# 02_-_IntelliModule_Connector.net
KiCad netlist of a schematic drawn in Altium Designer
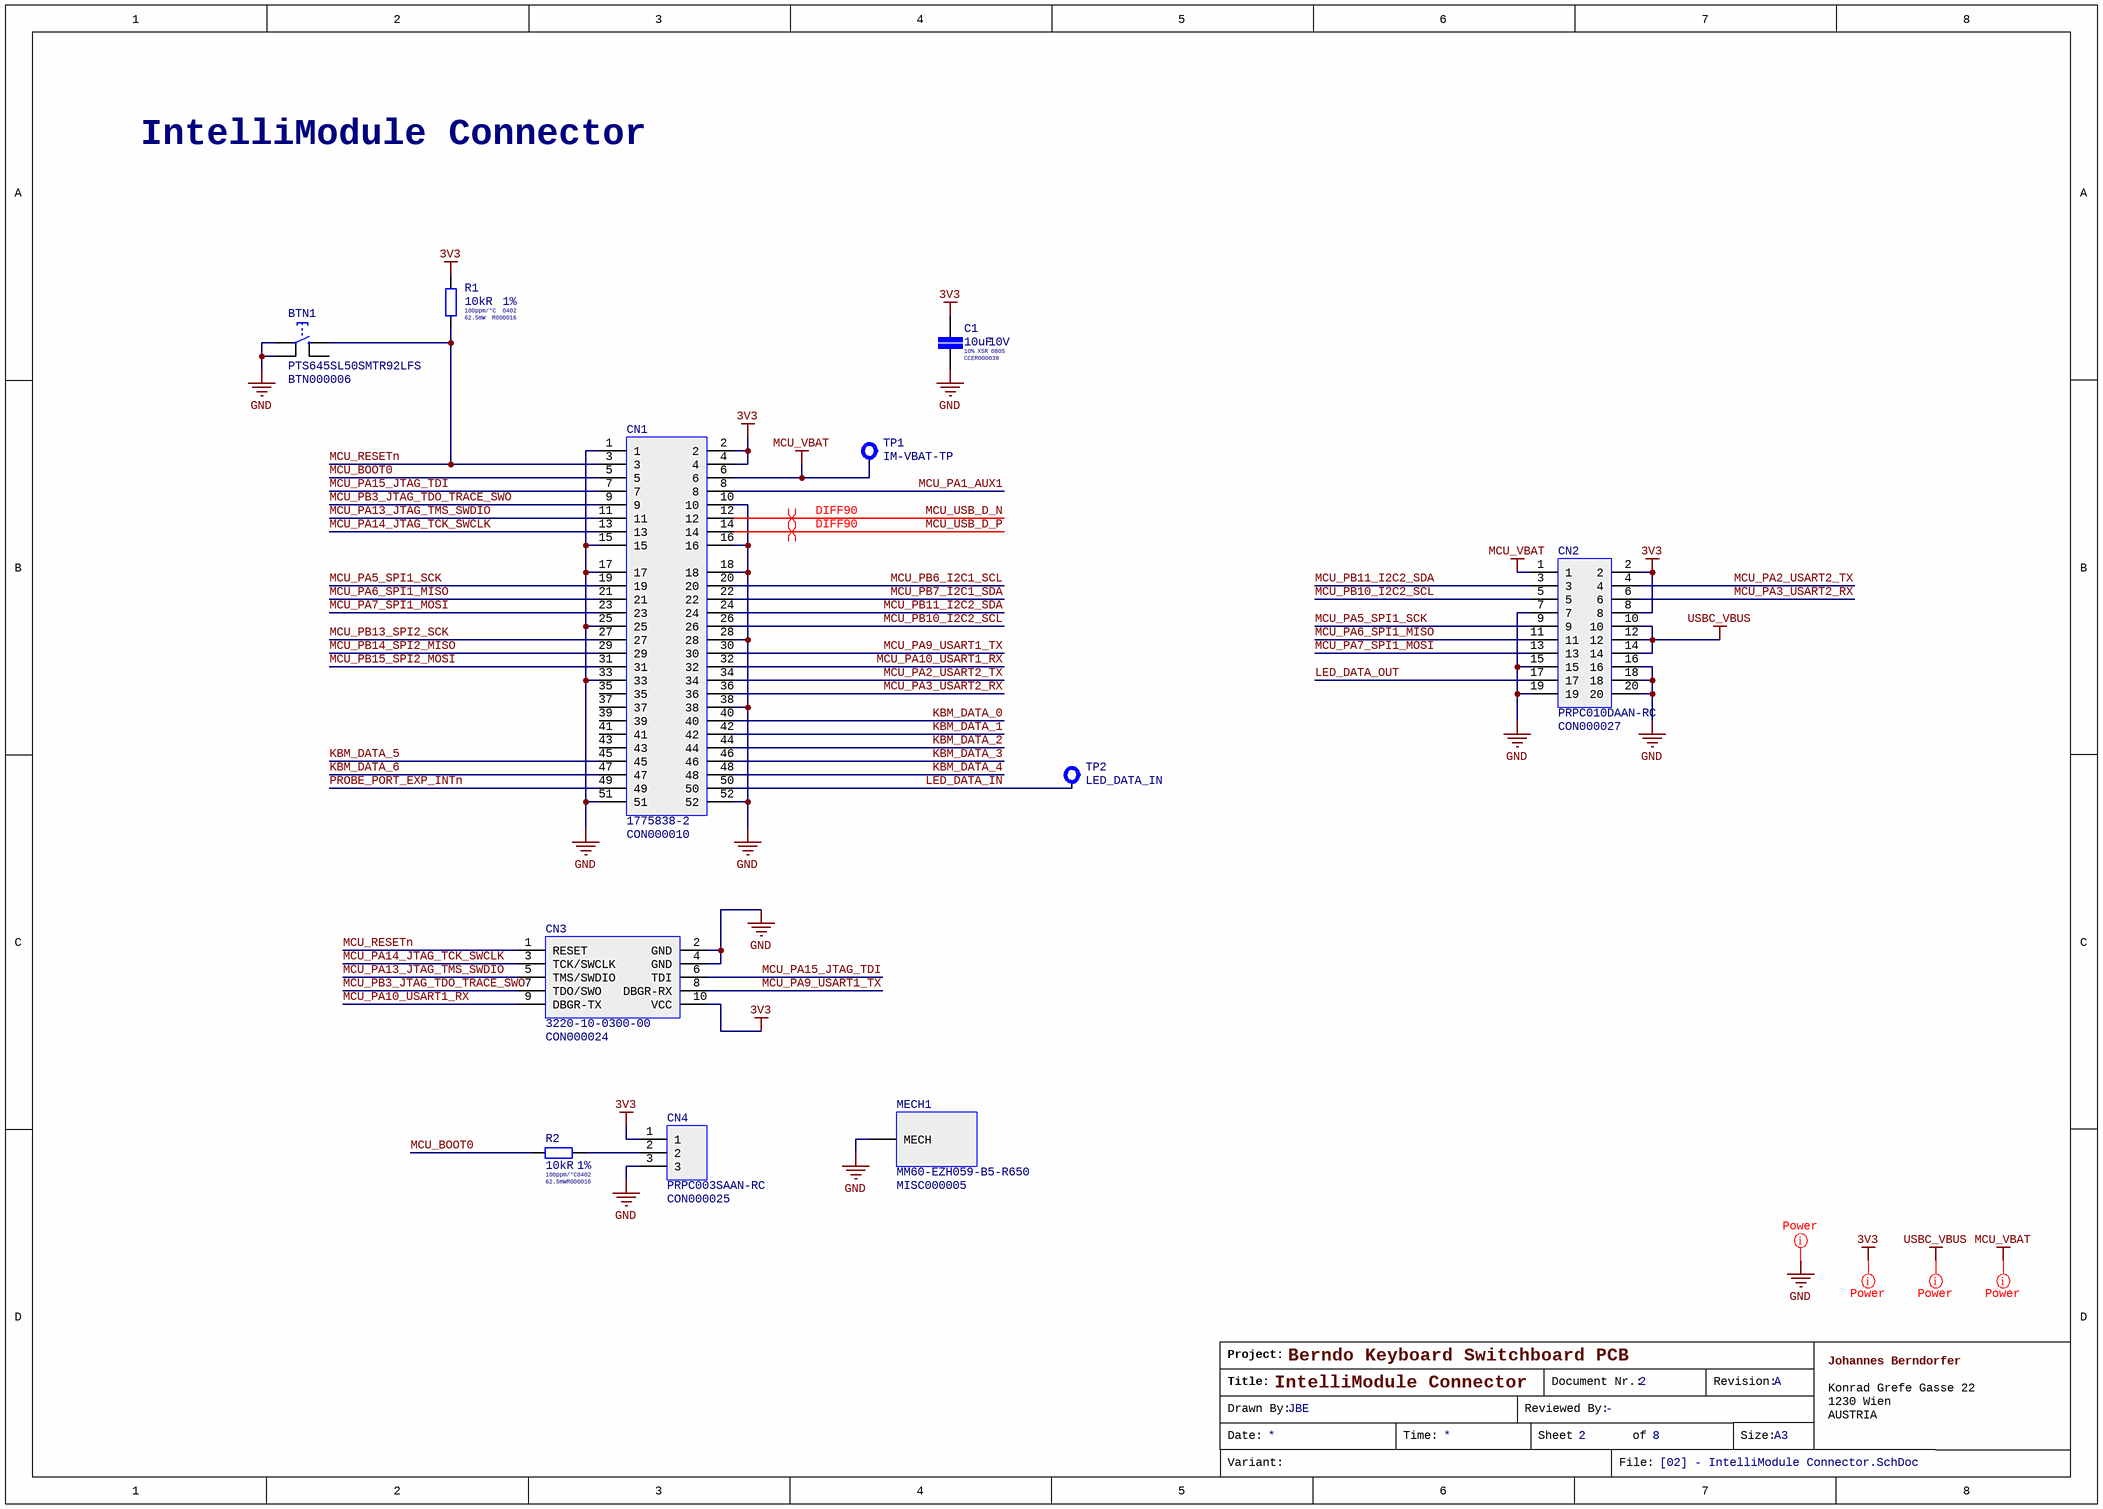
[diagram p0: [02] - IntelliModule Connector.SchDoc]

(export (version "E")
  (design (tool "Eeschema 10.0.6"))
  (components
    (comp (ref "BTN1")
      (value "PTS645SL50SMTR92LFS")
      (footprint "BTN-SMD-PTS645-CK")
      (description "BTN TACT SPST-NO 12V 50mA SMD BLACK")
      (fields (field (name "MANUFACTURER") "ITT C&K") (field (name "INTERNAL PART NUMBER") "BTN000006"))
      (libsource (lib "Altium_Lib_Standard") (part "PTS645SL50SMTR92LFS"))
    )
    (comp (ref "C1")
      (value "10uF 10V")
      (footprint "CAP-SMD-0805-1.35MM-IPC-MED")
      (description "CAP CER 10U 10V X5R 10% SMD 0805 85C SAMSUNG")
      (fields
        (field (name "VOLTAGE") "10V")
        (field (name "INTERNAL PART NUMBER") "CCER000039")
        (field (name "TOLERANCE") "10%")
        (field (name "VOLTAGE RATING") "10V")
        (field (name "DIELECTRIC") "X5R")
        (field (name "CASE/PACKAGE") "0805")
        (field (name "CAPACITANCE") "10uF")
      )
      (libsource (lib "Altium_Lib_Standard") (part "CL21A106KPFNNNG"))
    )
    (comp (ref "CN1")
      (value "1775838-2")
      (footprint "CON-SMD-PCIE-MINI-52POS-1775838-2-TE")
      (description "CON MINI PCIE CARD EDGE 52POS SMD")
      (fields (field (name "INTERNAL PART NUMBER") "CON000010"))
      (libsource (lib "Altium_Lib_Standard") (part "1775838-2"))
    )
    (comp (ref "CN2")
      (value "PRPC010DAAN-RC")
      (footprint "CON-THT-PINHEADER-2.54MM-20POS-2X10")
      (description "CON PINHDR 2.54MM 2x10")
      (fields (field (name "MANUFACTURER") "Sullins") (field (name "INTERNAL PART NUMBER") "CON000027"))
      (libsource (lib "Altium_Lib_Standard") (part "PRPC010DAAN-RC"))
    )
    (comp (ref "CN3")
      (value "3220-10-0300-00")
      (footprint "CON-SMD-PINHEADER-SHIELDED-1.27MM-10POS-2X5-3220-10-0300-00-CNC-TECH")
      (description "CON PINHDR SMD 1.27MM SHIELDED KEYED CNC TECH 10POS")
      (fields (field (name "INTERNAL PART NUMBER") "CON000024"))
      (libsource (lib "Altium_Lib_Standard") (part "3220-10-0300-00"))
    )
    (comp (ref "CN4")
      (value "PRPC003SAAN-RC")
      (footprint "CON-THT-PINHEADER-2.54MM-3POS-1X3")
      (description "CON PINHDR 2.54MM 1x03")
      (fields (field (name "MANUFACTURER") "Sullins") (field (name "INTERNAL PART NUMBER") "CON000025"))
      (libsource (lib "Altium_Lib_Standard") (part "PRPC003SAAN-RC"))
    )
    (comp (ref "MECH1")
      (value "MM60-EZH059-B5-R650")
      (footprint "CON-SMD-PCIE-MINI-LATCH-0POS-MM60-EZH059-B5-R650-JAE")
      (description "CARD LATCH MINI PCIE 3.05mm HEIGHT")
      (fields
        (field (name "MANUFACTURER") "JAE Electronics")
        (field (name "INTERNAL PART NUMBER") "MISC000005")
      )
      (libsource (lib "Altium_Lib_Standard") (part "MM60-EZH059-B5-R650"))
    )
    (comp (ref "R1")
      (value "10kR 1%")
      (footprint "RES-SMD-0402-0.4MM-IPC-MED")
      (description "RES 10K 1% 1/16W SMD 0402 YAEGO")
      (fields
        (field (name "MANUFACTURER") "Yageo")
        (field (name "MANUFACTURER PART NUMBER") "RC0402FR-0710KL")
        (field (name "TOLERANCE") "1%")
        (field (name "TEMPERATURE COEFFICIENT") "100ppm/°C")
        (field (name "RESISTANCE") "10kR")
        (field (name "POWER RATING") "62.5mW")
        (field (name "CASE CODE (IMPERIAL)") "0402")
        (field (name "INTERNAL PART NUMBER") "R000016")
      )
      (libsource (lib "Altium_Lib_Standard") (part "RC0402FR-0710KL"))
    )
    (comp (ref "R2")
      (value "10kR 1%")
      (footprint "RES-SMD-0402-0.4MM-IPC-MED")
      (description "RES 10K 1% 1/16W SMD 0402 YAEGO")
      (fields
        (field (name "MANUFACTURER") "Yageo")
        (field (name "MANUFACTURER PART NUMBER") "RC0402FR-0710KL")
        (field (name "TOLERANCE") "1%")
        (field (name "TEMPERATURE COEFFICIENT") "100ppm/°C")
        (field (name "RESISTANCE") "10kR")
        (field (name "POWER RATING") "62.5mW")
        (field (name "CASE CODE (IMPERIAL)") "0402")
        (field (name "INTERNAL PART NUMBER") "R000016")
      )
      (libsource (lib "Altium_Lib_Standard") (part "RC0402FR-0710KL"))
    )
    (comp (ref "TP1")
      (value "IM-VBAT-TP")
      (footprint "TP-SMD-CIRCULAR-1MM")
      (libsource (lib "Altium_Lib_Standard") (part "TESTPOINT_CIRCULAR_1MM"))
    )
    (comp (ref "TP2")
      (value "LED_DATA_IN")
      (footprint "TP-SMD-CIRCULAR-1MM")
      (libsource (lib "Altium_Lib_Standard") (part "TESTPOINT_CIRCULAR_1MM"))
    )
  )
  (nets
    (net (code "1") (name "/KBM_DATA_0") (class "Default")
      (node (ref "CN1") (pin "40") (pinfunction "40_40") (pintype "passive"))
    )
    (net (code "2") (name "/KBM_DATA_1") (class "Default")
      (node (ref "CN1") (pin "42") (pinfunction "42_42") (pintype "passive"))
    )
    (net (code "3") (name "/KBM_DATA_2") (class "Default")
      (node (ref "CN1") (pin "44") (pinfunction "44_44") (pintype "passive"))
    )
    (net (code "4") (name "/KBM_DATA_3") (class "Default")
      (node (ref "CN1") (pin "46") (pinfunction "46_46") (pintype "passive"))
    )
    (net (code "5") (name "/KBM_DATA_4") (class "Default")
      (node (ref "CN1") (pin "48") (pinfunction "48_48") (pintype "passive"))
    )
    (net (code "6") (name "/KBM_DATA_5") (class "Default")
      (node (ref "CN1") (pin "45") (pinfunction "45_45") (pintype "passive"))
    )
    (net (code "7") (name "/KBM_DATA_6") (class "Default")
      (node (ref "CN1") (pin "47") (pinfunction "47_47") (pintype "passive"))
    )
    (net (code "8") (name "/LED_DATA_IN") (class "Default")
      (node (ref "CN1") (pin "50") (pinfunction "50_50") (pintype "passive"))
      (node (ref "TP2") (pin "1") (pinfunction "1_1") (pintype "passive"))
    )
    (net (code "9") (name "/LED_DATA_OUT") (class "Default")
      (node (ref "CN2") (pin "17") (pinfunction "17_17") (pintype "passive"))
    )
    (net (code "10") (name "/MCU_BOOT0") (class "Default")
      (node (ref "CN1") (pin "5") (pinfunction "5_5") (pintype "passive"))
      (node (ref "R2") (pin "1") (pinfunction "1_1") (pintype "passive"))
    )
    (net (code "11") (name "/MCU_PA1_AUX1") (class "Default")
      (node (ref "CN1") (pin "8") (pinfunction "8_8") (pintype "passive"))
    )
    (net (code "12") (name "/MCU_PA2_USART2_TX") (class "Default")
      (node (ref "CN1") (pin "34") (pinfunction "34_34") (pintype "passive"))
      (node (ref "CN2") (pin "4") (pinfunction "4_4") (pintype "passive"))
    )
    (net (code "13") (name "/MCU_PA3_USART2_RX") (class "Default")
      (node (ref "CN1") (pin "36") (pinfunction "36_36") (pintype "passive"))
      (node (ref "CN2") (pin "6") (pinfunction "6_6") (pintype "passive"))
    )
    (net (code "14") (name "/MCU_PA5_SPI1_SCK") (class "Default")
      (node (ref "CN1") (pin "19") (pinfunction "19_19") (pintype "passive"))
      (node (ref "CN2") (pin "9") (pinfunction "9_9") (pintype "passive"))
    )
    (net (code "15") (name "/MCU_PA6_SPI1_MISO") (class "Default")
      (node (ref "CN1") (pin "21") (pinfunction "21_21") (pintype "passive"))
      (node (ref "CN2") (pin "11") (pinfunction "11_11") (pintype "passive"))
    )
    (net (code "16") (name "/MCU_PA7_SPI1_MOSI") (class "Default")
      (node (ref "CN1") (pin "23") (pinfunction "23_23") (pintype "passive"))
      (node (ref "CN2") (pin "13") (pinfunction "13_13") (pintype "passive"))
    )
    (net (code "17") (name "/MCU_PA9_USART1_TX") (class "Default")
      (node (ref "CN1") (pin "30") (pinfunction "30_30") (pintype "passive"))
      (node (ref "CN3") (pin "8") (pinfunction "DBGR-RX_8") (pintype "passive"))
    )
    (net (code "18") (name "/MCU_PA10_USART1_RX") (class "Default")
      (node (ref "CN1") (pin "32") (pinfunction "32_32") (pintype "passive"))
      (node (ref "CN3") (pin "9") (pinfunction "DBGR-TX_9") (pintype "passive"))
    )
    (net (code "19") (name "/MCU_PA13_JTAG_TMS_SWDIO") (class "Default")
      (node (ref "CN1") (pin "11") (pinfunction "11_11") (pintype "passive"))
      (node (ref "CN3") (pin "5") (pinfunction "TMS/SWDIO_5") (pintype "passive"))
    )
    (net (code "20") (name "/MCU_PA14_JTAG_TCK_SWCLK") (class "Default")
      (node (ref "CN1") (pin "13") (pinfunction "13_13") (pintype "passive"))
      (node (ref "CN3") (pin "3") (pinfunction "TCK/SWCLK_3") (pintype "passive"))
    )
    (net (code "21") (name "/MCU_PA15_JTAG_TDI") (class "Default")
      (node (ref "CN1") (pin "7") (pinfunction "7_7") (pintype "passive"))
      (node (ref "CN3") (pin "6") (pinfunction "TDI_6") (pintype "passive"))
    )
    (net (code "22") (name "/MCU_PB3_JTAG_TDO_TRACE_SWO") (class "Default")
      (node (ref "CN1") (pin "9") (pinfunction "9_9") (pintype "passive"))
      (node (ref "CN3") (pin "7") (pinfunction "TDO/SWO_7") (pintype "passive"))
    )
    (net (code "23") (name "/MCU_PB6_I2C1_SCL") (class "Default")
      (node (ref "CN1") (pin "20") (pinfunction "20_20") (pintype "passive"))
    )
    (net (code "24") (name "/MCU_PB7_I2C1_SDA") (class "Default")
      (node (ref "CN1") (pin "22") (pinfunction "22_22") (pintype "passive"))
    )
    (net (code "25") (name "/MCU_PB10_I2C2_SCL") (class "Default")
      (node (ref "CN1") (pin "26") (pinfunction "26_26") (pintype "passive"))
      (node (ref "CN2") (pin "5") (pinfunction "5_5") (pintype "passive"))
    )
    (net (code "26") (name "/MCU_PB11_I2C2_SDA") (class "Default")
      (node (ref "CN1") (pin "24") (pinfunction "24_24") (pintype "passive"))
      (node (ref "CN2") (pin "3") (pinfunction "3_3") (pintype "passive"))
    )
    (net (code "27") (name "/MCU_PB13_SPI2_SCK") (class "Default")
      (node (ref "CN1") (pin "27") (pinfunction "27_27") (pintype "passive"))
    )
    (net (code "28") (name "/MCU_PB14_SPI2_MISO") (class "Default")
      (node (ref "CN1") (pin "29") (pinfunction "29_29") (pintype "passive"))
    )
    (net (code "29") (name "/MCU_PB15_SPI2_MOSI") (class "Default")
      (node (ref "CN1") (pin "31") (pinfunction "31_31") (pintype "passive"))
    )
    (net (code "30") (name "/MCU_RESETn") (class "Default")
      (node (ref "BTN1") (pin "3") (pinfunction "3_3") (pintype "passive"))
      (node (ref "CN1") (pin "3") (pinfunction "3_3") (pintype "passive"))
      (node (ref "CN3") (pin "1") (pinfunction "RESET_1") (pintype "passive"))
      (node (ref "R1") (pin "2") (pinfunction "2_2") (pintype "passive"))
    )
    (net (code "31") (name "/MCU_USB_D_N") (class "Default")
      (node (ref "CN1") (pin "12") (pinfunction "12_12") (pintype "passive"))
    )
    (net (code "32") (name "/MCU_USB_D_P") (class "Default")
      (node (ref "CN1") (pin "14") (pinfunction "14_14") (pintype "passive"))
    )
    (net (code "33") (name "/PROBE_PORT_EXP_INTn") (class "Default")
      (node (ref "CN1") (pin "49") (pinfunction "49_49") (pintype "passive"))
    )
    (net (code "34") (name "3V3") (class "Default")
      (node (ref "C1") (pin "1") (pinfunction "1_1") (pintype "passive"))
      (node (ref "CN1") (pin "2") (pinfunction "2_2") (pintype "passive"))
      (node (ref "CN1") (pin "4") (pinfunction "4_4") (pintype "passive"))
      (node (ref "CN2") (pin "2") (pinfunction "2_2") (pintype "passive"))
      (node (ref "CN2") (pin "8") (pinfunction "8_8") (pintype "passive"))
      (node (ref "CN3") (pin "10") (pinfunction "VCC_10") (pintype "passive"))
      (node (ref "CN4") (pin "1") (pinfunction "1_1") (pintype "passive"))
      (node (ref "R1") (pin "1") (pinfunction "1_1") (pintype "passive"))
    )
    (net (code "35") (name "GND") (class "Default")
      (node (ref "BTN1") (pin "1") (pinfunction "1_1") (pintype "passive"))
      (node (ref "BTN1") (pin "2") (pinfunction "2_2") (pintype "passive"))
      (node (ref "C1") (pin "2") (pinfunction "2_2") (pintype "passive"))
      (node (ref "CN1") (pin "1") (pinfunction "1_1") (pintype "passive"))
      (node (ref "CN1") (pin "10") (pinfunction "10_10") (pintype "passive"))
      (node (ref "CN1") (pin "15") (pinfunction "15_15") (pintype "passive"))
      (node (ref "CN1") (pin "16") (pinfunction "16_16") (pintype "passive"))
      (node (ref "CN1") (pin "17") (pinfunction "17_17") (pintype "passive"))
      (node (ref "CN1") (pin "18") (pinfunction "18_18") (pintype "passive"))
      (node (ref "CN1") (pin "25") (pinfunction "25_25") (pintype "passive"))
      (node (ref "CN1") (pin "28") (pinfunction "28_28") (pintype "passive"))
      (node (ref "CN1") (pin "33") (pinfunction "33_33") (pintype "passive"))
      (node (ref "CN1") (pin "38") (pinfunction "38_38") (pintype "passive"))
      (node (ref "CN1") (pin "51") (pinfunction "51_51") (pintype "passive"))
      (node (ref "CN1") (pin "52") (pinfunction "52_52") (pintype "passive"))
      (node (ref "CN2") (pin "15") (pinfunction "15_15") (pintype "passive"))
      (node (ref "CN2") (pin "16") (pinfunction "16_16") (pintype "passive"))
      (node (ref "CN2") (pin "18") (pinfunction "18_18") (pintype "passive"))
      (node (ref "CN2") (pin "19") (pinfunction "19_19") (pintype "passive"))
      (node (ref "CN2") (pin "20") (pinfunction "20_20") (pintype "passive"))
      (node (ref "CN2") (pin "7") (pinfunction "7_7") (pintype "passive"))
      (node (ref "CN3") (pin "2") (pinfunction "GND_2") (pintype "passive"))
      (node (ref "CN3") (pin "4") (pinfunction "GND_4") (pintype "passive"))
      (node (ref "CN4") (pin "3") (pinfunction "3_3") (pintype "passive"))
      (node (ref "MECH1") (pin "0") (pinfunction "MECH_0") (pintype "passive"))
    )
    (net (code "36") (name "MCU_VBAT") (class "Default")
      (node (ref "CN1") (pin "6") (pinfunction "6_6") (pintype "passive"))
      (node (ref "CN2") (pin "1") (pinfunction "1_1") (pintype "passive"))
      (node (ref "TP1") (pin "1") (pinfunction "1_1") (pintype "passive"))
    )
    (net (code "37") (name "Net-(CN4-Pad2)") (class "Default")
      (node (ref "CN4") (pin "2") (pinfunction "2_2") (pintype "passive"))
      (node (ref "R2") (pin "2") (pinfunction "2_2") (pintype "passive"))
    )
    (net (code "38") (name "USBC_VBUS") (class "Default")
      (node (ref "CN2") (pin "10") (pinfunction "10_10") (pintype "passive"))
      (node (ref "CN2") (pin "12") (pinfunction "12_12") (pintype "passive"))
      (node (ref "CN2") (pin "14") (pinfunction "14_14") (pintype "passive"))
    )
    (net (code "39") (name "unconnected-(BTN1-Pad4)") (class "Default")
      (node (ref "BTN1") (pin "4") (pinfunction "4_4") (pintype "passive"))
    )
    (net (code "40") (name "unconnected-(CN1-Pad35)") (class "Default")
      (node (ref "CN1") (pin "35") (pinfunction "35_35") (pintype "passive"))
    )
    (net (code "41") (name "unconnected-(CN1-Pad37)") (class "Default")
      (node (ref "CN1") (pin "37") (pinfunction "37_37") (pintype "passive"))
    )
    (net (code "42") (name "unconnected-(CN1-Pad39)") (class "Default")
      (node (ref "CN1") (pin "39") (pinfunction "39_39") (pintype "passive"))
    )
    (net (code "43") (name "unconnected-(CN1-Pad41)") (class "Default")
      (node (ref "CN1") (pin "41") (pinfunction "41_41") (pintype "passive"))
    )
    (net (code "44") (name "unconnected-(CN1-Pad43)") (class "Default")
      (node (ref "CN1") (pin "43") (pinfunction "43_43") (pintype "passive"))
    )
  )
)
